# mains_led.net
KiCad netlist of a schematic drawn in EAGLE
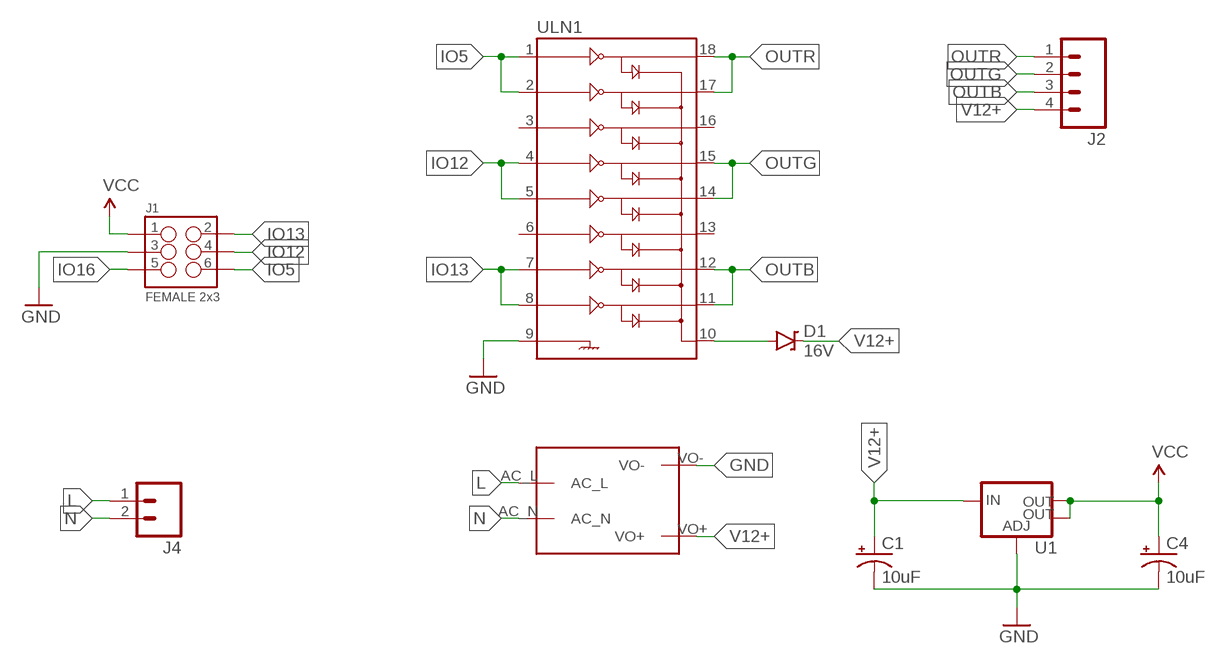
[diagram p0: schematic, sheet 1]

(export (version "E")
  (design (tool "Eeschema 10.0.6"))
  (components
    (comp (ref "C1")
      (value "10uF")
      (footprint "eagle-import:EIA3216-KIT")
      (libsource (lib "eagle-import") (part "CAP_POL1206-KIT"))
    )
    (comp (ref "C4")
      (value "10uF")
      (footprint "eagle-import:EIA3216-KIT")
      (libsource (lib "eagle-import") (part "CAP_POL1206-KIT"))
    )
    (comp (ref "D1")
      (value "16V")
      (footprint "eagle-import:SOD-123")
      (libsource (lib "eagle-import") (part "DIODE-ZENER16V"))
    )
    (comp (ref "J1")
      (value "FEMALE 2x3")
      (footprint "eagle-import:2X3-SHROUDED")
      (libsource (lib "eagle-import") (part "M03X2SHROUD"))
    )
    (comp (ref "J2")
      (value "M04NO_SILK_ALL_ROUND")
      (footprint "eagle-import:1X04_NO_SILK_ALL_ROUND")
      (libsource (lib "eagle-import") (part "M04NO_SILK_ALL_ROUND"))
    )
    (comp (ref "J4")
      (value "M023.5MM")
      (footprint "eagle-import:SCREWTERMINAL-3.5MM-2")
      (libsource (lib "eagle-import") (part "M023.5MM"))
    )
    (comp (ref "U$1")
      (value "MAINS_CONVERTERS")
      (footprint "eagle-import:HLK-PM01")
      (libsource (lib "eagle-import") (part "MAINS_CONVERTERS"))
    )
    (comp (ref "U1")
      (value "V_REG_LM1117SOT223")
      (footprint "eagle-import:SOT223")
      (libsource (lib "eagle-import") (part "V_REG_LM1117SOT223"))
    )
    (comp (ref "ULN1")
      (value "ULN2803SOICW")
      (footprint "eagle-import:SO18L")
      (libsource (lib "eagle-import") (part "ULN2803SOICW"))
    )
  )
  (nets
    (net (code "1") (name "GND") (class "Default")
      (node (ref "C1") (pin "C") (pinfunction "-_C") (pintype "passive"))
      (node (ref "C4") (pin "C") (pinfunction "-_C") (pintype "passive"))
      (node (ref "J1") (pin "3") (pinfunction "3_3") (pintype "bidirectional"))
      (node (ref "U$1") (pin "VO-") (pinfunction "VO-_VO-") (pintype "output"))
      (node (ref "U1") (pin "1") (pinfunction "ADJ_1") (pintype "input"))
      (node (ref "ULN1") (pin "9") (pinfunction "9_9") (pintype "bidirectional"))
    )
    (net (code "2") (name "IO5") (class "Default")
      (node (ref "J1") (pin "6") (pinfunction "6_6") (pintype "bidirectional"))
      (node (ref "ULN1") (pin "1") (pinfunction "1_1") (pintype "bidirectional"))
      (node (ref "ULN1") (pin "2") (pinfunction "2_2") (pintype "bidirectional"))
    )
    (net (code "3") (name "IO12") (class "Default")
      (node (ref "J1") (pin "4") (pinfunction "4_4") (pintype "bidirectional"))
      (node (ref "ULN1") (pin "4") (pinfunction "4_4") (pintype "bidirectional"))
      (node (ref "ULN1") (pin "5") (pinfunction "5_5") (pintype "bidirectional"))
    )
    (net (code "4") (name "IO13") (class "Default")
      (node (ref "J1") (pin "2") (pinfunction "2_2") (pintype "bidirectional"))
      (node (ref "ULN1") (pin "7") (pinfunction "7_7") (pintype "bidirectional"))
      (node (ref "ULN1") (pin "8") (pinfunction "8_8") (pintype "bidirectional"))
    )
    (net (code "5") (name "IO16") (class "Default")
      (node (ref "J1") (pin "5") (pinfunction "5_5") (pintype "bidirectional"))
    )
    (net (code "6") (name "L") (class "Default")
      (node (ref "J4") (pin "1") (pinfunction "1_1") (pintype "passive"))
      (node (ref "U$1") (pin "AC_L") (pinfunction "AC_L_AC_L") (pintype "input"))
    )
    (net (code "7") (name "N") (class "Default")
      (node (ref "J4") (pin "2") (pinfunction "2_2") (pintype "passive"))
      (node (ref "U$1") (pin "AC_N") (pinfunction "AC_N_AC_N") (pintype "input"))
    )
    (net (code "8") (name "Net-(D1-PadA)") (class "Default")
      (node (ref "D1") (pin "A") (pinfunction "A_A") (pintype "passive"))
      (node (ref "ULN1") (pin "10") (pinfunction "10_10") (pintype "bidirectional"))
    )
    (net (code "9") (name "OUTB") (class "Default")
      (node (ref "J2") (pin "3") (pinfunction "3_3") (pintype "passive"))
      (node (ref "ULN1") (pin "11") (pinfunction "11_11") (pintype "bidirectional"))
      (node (ref "ULN1") (pin "12") (pinfunction "12_12") (pintype "bidirectional"))
    )
    (net (code "10") (name "OUTG") (class "Default")
      (node (ref "J2") (pin "2") (pinfunction "2_2") (pintype "passive"))
      (node (ref "ULN1") (pin "14") (pinfunction "14_14") (pintype "bidirectional"))
      (node (ref "ULN1") (pin "15") (pinfunction "15_15") (pintype "bidirectional"))
    )
    (net (code "11") (name "OUTR") (class "Default")
      (node (ref "J2") (pin "1") (pinfunction "1_1") (pintype "passive"))
      (node (ref "ULN1") (pin "17") (pinfunction "17_17") (pintype "bidirectional"))
      (node (ref "ULN1") (pin "18") (pinfunction "18_18") (pintype "bidirectional"))
    )
    (net (code "12") (name "V12+") (class "Default")
      (node (ref "C1") (pin "A") (pinfunction "+_A") (pintype "passive"))
      (node (ref "D1") (pin "C") (pinfunction "C_C") (pintype "passive"))
      (node (ref "J2") (pin "4") (pinfunction "4_4") (pintype "passive"))
      (node (ref "U$1") (pin "VO+") (pinfunction "VO+_VO+") (pintype "output"))
      (node (ref "U1") (pin "3") (pinfunction "IN_3") (pintype "input"))
    )
    (net (code "13") (name "VCC") (class "Default")
      (node (ref "C4") (pin "A") (pinfunction "+_A") (pintype "passive"))
      (node (ref "J1") (pin "1") (pinfunction "1_1") (pintype "bidirectional"))
      (node (ref "U1") (pin "2") (pinfunction "OUT_2") (pintype "output"))
      (node (ref "U1") (pin "4") (pinfunction "OUT_4") (pintype "output"))
    )
    (net (code "14") (name "unconnected-(ULN1-Pad3)") (class "Default")
      (node (ref "ULN1") (pin "3") (pinfunction "3_3") (pintype "bidirectional"))
    )
    (net (code "15") (name "unconnected-(ULN1-Pad6)") (class "Default")
      (node (ref "ULN1") (pin "6") (pinfunction "6_6") (pintype "bidirectional"))
    )
    (net (code "16") (name "unconnected-(ULN1-Pad13)") (class "Default")
      (node (ref "ULN1") (pin "13") (pinfunction "13_13") (pintype "bidirectional"))
    )
    (net (code "17") (name "unconnected-(ULN1-Pad16)") (class "Default")
      (node (ref "ULN1") (pin "16") (pinfunction "16_16") (pintype "bidirectional"))
    )
  )
)
